# LDA_Board.net
KiCad netlist of a schematic drawn in EAGLE
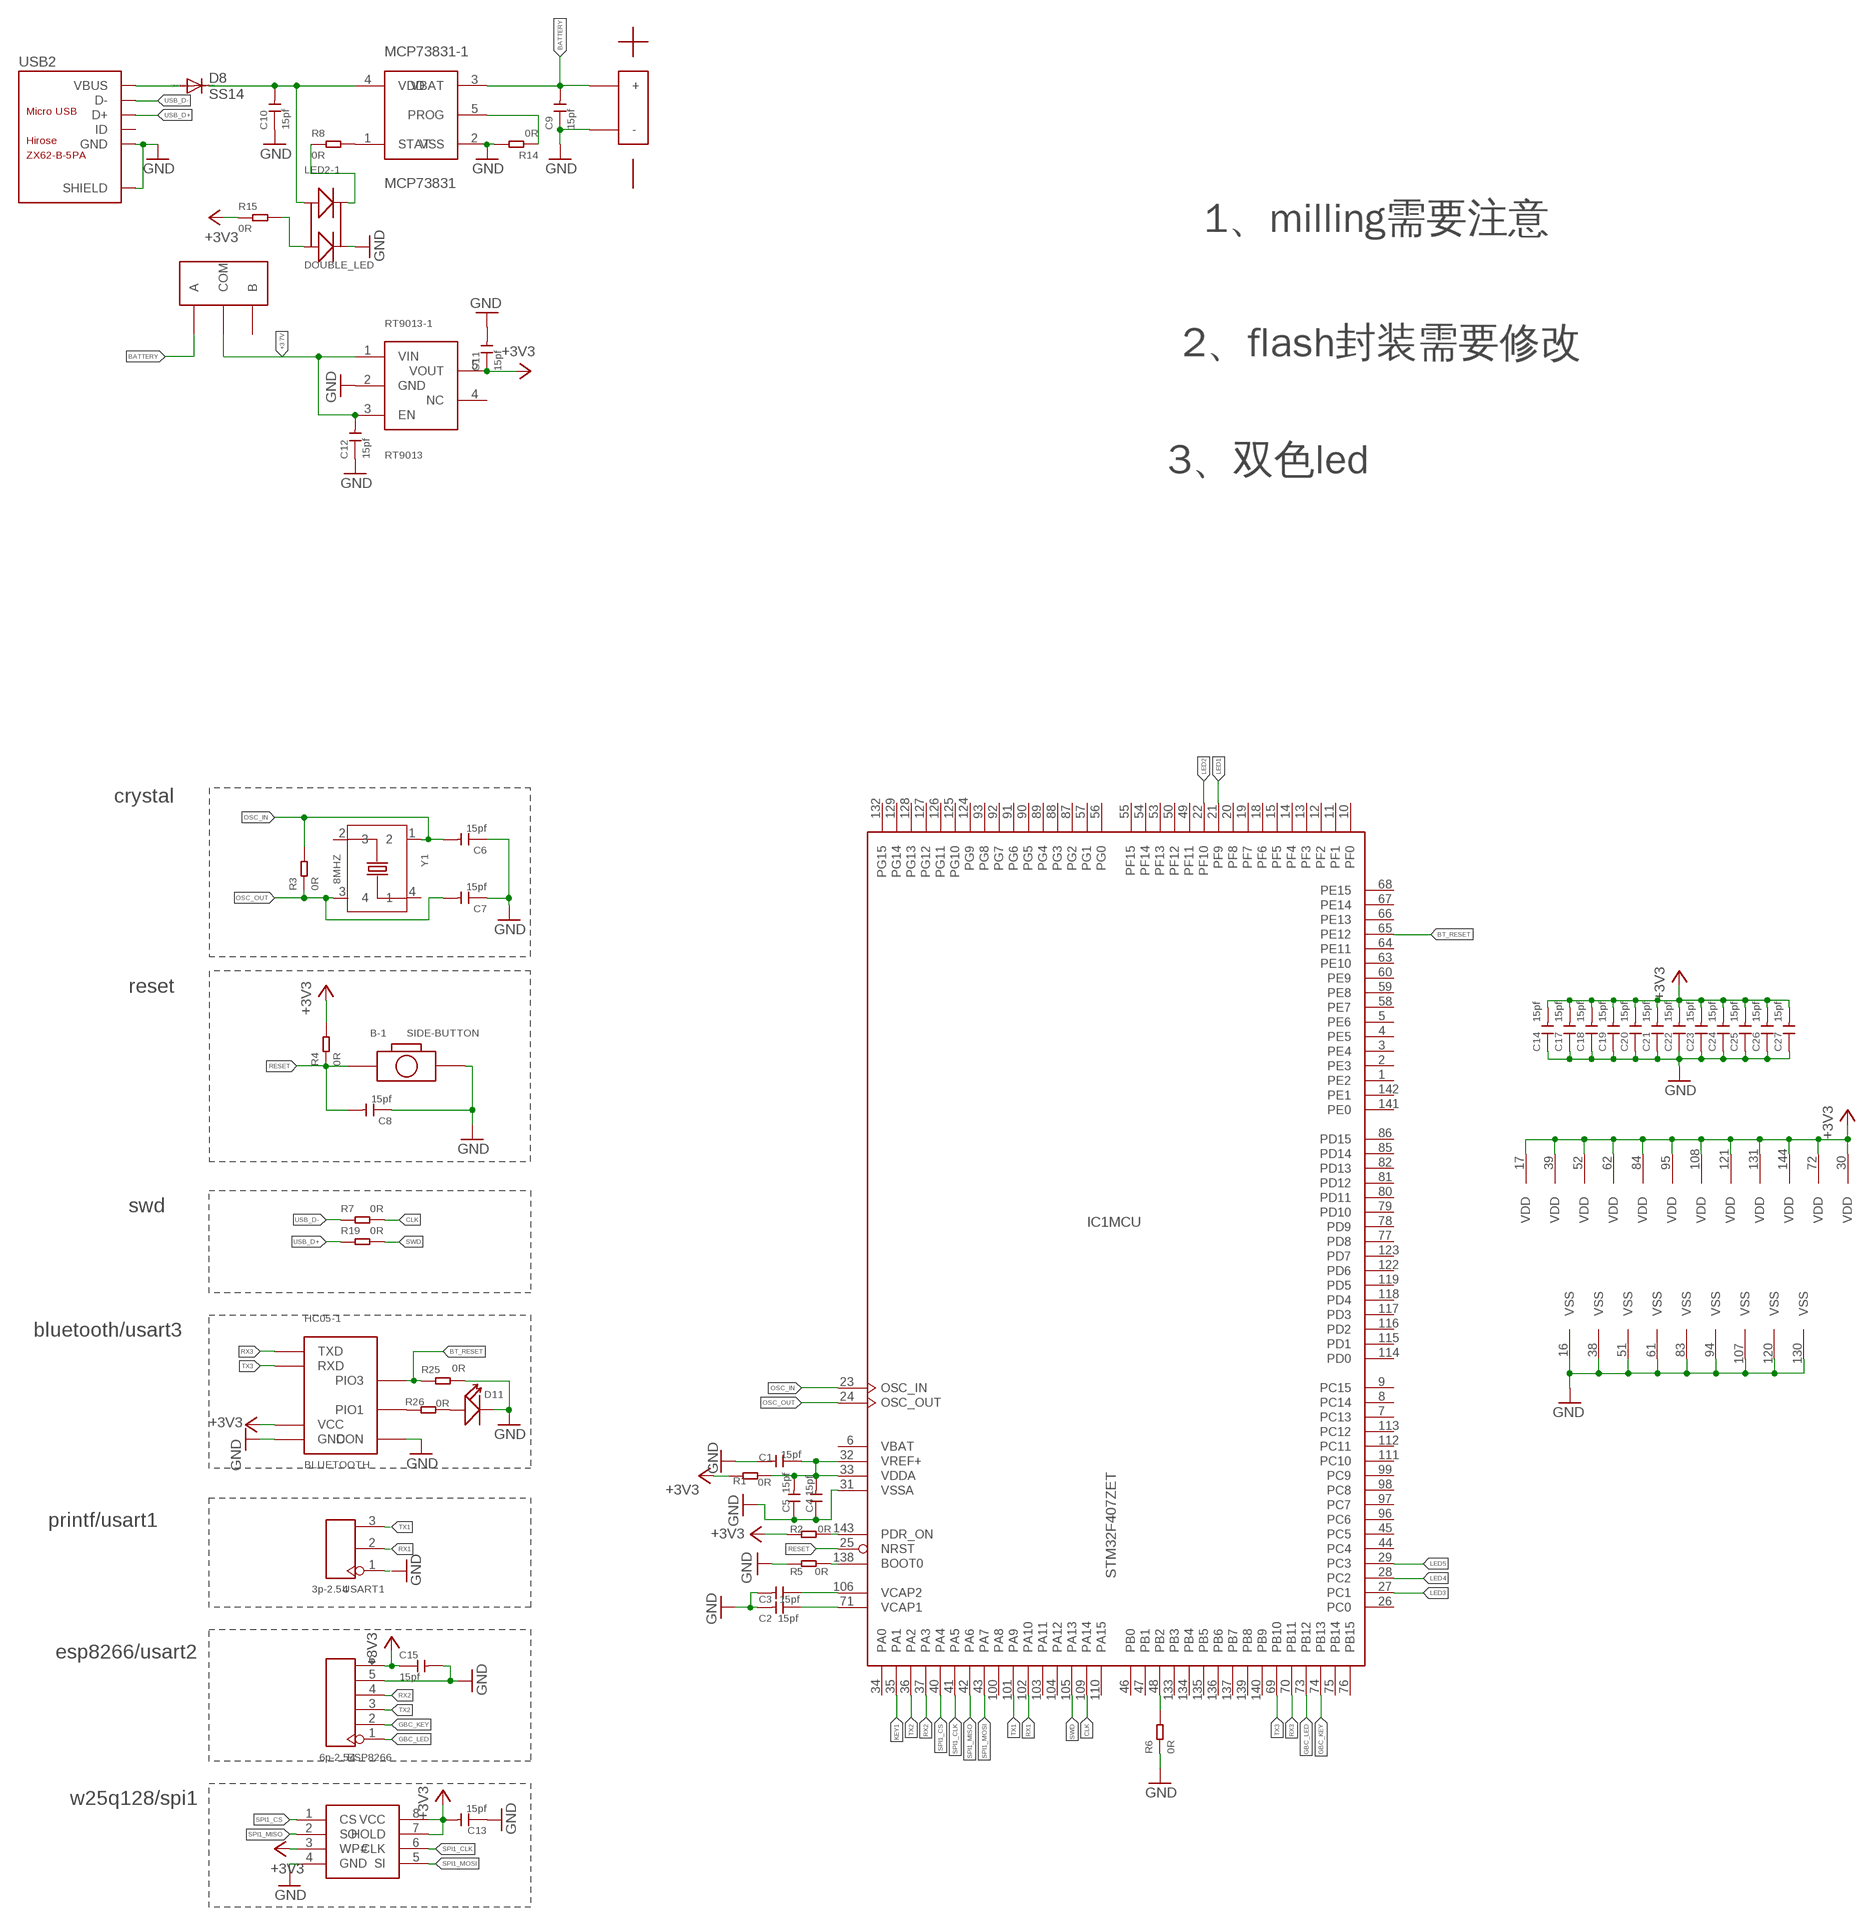
[diagram p0: schematic, sheet 1, part 1 of 2]
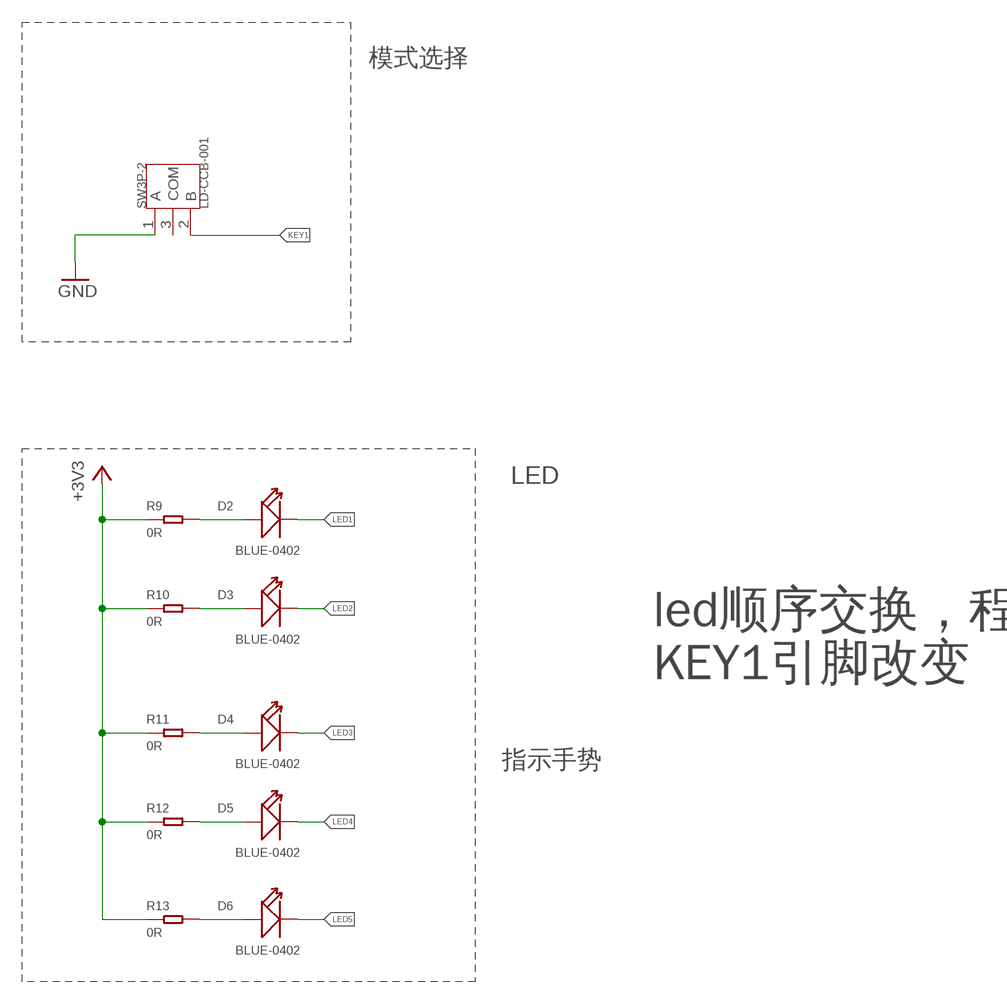
[diagram p1: schematic, sheet 1, part 2 of 2]

(export (version "E")
  (design (tool "Eeschema 10.0.6"))
  (components
    (comp (ref "B-1")
      (value "SIDE-BUTTON")
      (footprint "eagle-import:SIDE-BUTTON")
      (libsource (lib "eagle-import") (part "SIDE-BUTTON"))
    )
    (comp (ref "BATTERY-1")
      (value "BATTERY")
      (footprint "eagle-import:BATTERY")
      (libsource (lib "eagle-import") (part "BATTERY"))
    )
    (comp (ref "C1")
      (value "15pf")
      (footprint "eagle-import:C0402")
      (fields (field (name "MPN") "GRM1555C1H150JA01D"))
      (libsource (lib "eagle-import") (part "CAP-(0402)"))
    )
    (comp (ref "C2")
      (value "15pf")
      (footprint "eagle-import:C0402")
      (fields (field (name "MPN") "GRM1555C1H150JA01D"))
      (libsource (lib "eagle-import") (part "CAP-(0402)"))
    )
    (comp (ref "C3")
      (value "15pf")
      (footprint "eagle-import:C0402")
      (fields (field (name "MPN") "GRM1555C1H150JA01D"))
      (libsource (lib "eagle-import") (part "CAP-(0402)"))
    )
    (comp (ref "C4")
      (value "15pf")
      (footprint "eagle-import:C0402")
      (fields (field (name "MPN") "GRM1555C1H150JA01D"))
      (libsource (lib "eagle-import") (part "CAP-(0402)"))
    )
    (comp (ref "C5")
      (value "15pf")
      (footprint "eagle-import:C0402")
      (fields (field (name "MPN") "GRM1555C1H150JA01D"))
      (libsource (lib "eagle-import") (part "CAP-(0402)"))
    )
    (comp (ref "C6")
      (value "15pf")
      (footprint "eagle-import:C0402")
      (fields (field (name "MPN") "GRM1555C1H150JA01D"))
      (libsource (lib "eagle-import") (part "CAP-(0402)"))
    )
    (comp (ref "C7")
      (value "15pf")
      (footprint "eagle-import:C0402")
      (fields (field (name "MPN") "GRM1555C1H150JA01D"))
      (libsource (lib "eagle-import") (part "CAP-(0402)"))
    )
    (comp (ref "C8")
      (value "15pf")
      (footprint "eagle-import:C0402")
      (fields (field (name "MPN") "GRM1555C1H150JA01D"))
      (libsource (lib "eagle-import") (part "CAP-(0402)"))
    )
    (comp (ref "C9")
      (value "15pf")
      (footprint "eagle-import:C0402")
      (fields (field (name "MPN") "GRM1555C1H150JA01D"))
      (libsource (lib "eagle-import") (part "CAP-(0402)"))
    )
    (comp (ref "C10")
      (value "15pf")
      (footprint "eagle-import:C0402")
      (fields (field (name "MPN") "GRM1555C1H150JA01D"))
      (libsource (lib "eagle-import") (part "CAP-(0402)"))
    )
    (comp (ref "C11")
      (value "15pf")
      (footprint "eagle-import:C0402")
      (fields (field (name "MPN") "GRM1555C1H150JA01D"))
      (libsource (lib "eagle-import") (part "CAP-(0402)"))
    )
    (comp (ref "C12")
      (value "15pf")
      (footprint "eagle-import:C0402")
      (fields (field (name "MPN") "GRM1555C1H150JA01D"))
      (libsource (lib "eagle-import") (part "CAP-(0402)"))
    )
    (comp (ref "C13")
      (value "15pf")
      (footprint "eagle-import:C0402")
      (fields (field (name "MPN") "GRM1555C1H150JA01D"))
      (libsource (lib "eagle-import") (part "CAP-(0402)"))
    )
    (comp (ref "C14")
      (value "15pf")
      (footprint "eagle-import:C0402")
      (fields (field (name "MPN") "GRM1555C1H150JA01D"))
      (libsource (lib "eagle-import") (part "CAP-(0402)"))
    )
    (comp (ref "C15")
      (value "15pf")
      (footprint "eagle-import:C0402")
      (fields (field (name "MPN") "GRM1555C1H150JA01D"))
      (libsource (lib "eagle-import") (part "CAP-(0402)"))
    )
    (comp (ref "C17")
      (value "15pf")
      (footprint "eagle-import:C0402")
      (fields (field (name "MPN") "GRM1555C1H150JA01D"))
      (libsource (lib "eagle-import") (part "CAP-(0402)"))
    )
    (comp (ref "C18")
      (value "15pf")
      (footprint "eagle-import:C0402")
      (fields (field (name "MPN") "GRM1555C1H150JA01D"))
      (libsource (lib "eagle-import") (part "CAP-(0402)"))
    )
    (comp (ref "C19")
      (value "15pf")
      (footprint "eagle-import:C0402")
      (fields (field (name "MPN") "GRM1555C1H150JA01D"))
      (libsource (lib "eagle-import") (part "CAP-(0402)"))
    )
    (comp (ref "C20")
      (value "15pf")
      (footprint "eagle-import:C0402")
      (fields (field (name "MPN") "GRM1555C1H150JA01D"))
      (libsource (lib "eagle-import") (part "CAP-(0402)"))
    )
    (comp (ref "C21")
      (value "15pf")
      (footprint "eagle-import:C0402")
      (fields (field (name "MPN") "GRM1555C1H150JA01D"))
      (libsource (lib "eagle-import") (part "CAP-(0402)"))
    )
    (comp (ref "C22")
      (value "15pf")
      (footprint "eagle-import:C0402")
      (fields (field (name "MPN") "GRM1555C1H150JA01D"))
      (libsource (lib "eagle-import") (part "CAP-(0402)"))
    )
    (comp (ref "C23")
      (value "15pf")
      (footprint "eagle-import:C0402")
      (fields (field (name "MPN") "GRM1555C1H150JA01D"))
      (libsource (lib "eagle-import") (part "CAP-(0402)"))
    )
    (comp (ref "C24")
      (value "15pf")
      (footprint "eagle-import:C0402")
      (fields (field (name "MPN") "GRM1555C1H150JA01D"))
      (libsource (lib "eagle-import") (part "CAP-(0402)"))
    )
    (comp (ref "C25")
      (value "15pf")
      (footprint "eagle-import:C0402")
      (fields (field (name "MPN") "GRM1555C1H150JA01D"))
      (libsource (lib "eagle-import") (part "CAP-(0402)"))
    )
    (comp (ref "C26")
      (value "15pf")
      (footprint "eagle-import:C0402")
      (fields (field (name "MPN") "GRM1555C1H150JA01D"))
      (libsource (lib "eagle-import") (part "CAP-(0402)"))
    )
    (comp (ref "C27")
      (value "15pf")
      (footprint "eagle-import:C0402")
      (fields (field (name "MPN") "GRM1555C1H150JA01D"))
      (libsource (lib "eagle-import") (part "CAP-(0402)"))
    )
    (comp (ref "D2")
      (value "BLUE-0402")
      (footprint "eagle-import:LED-0402")
      (fields (field (name "MPN") "BL-HB337A-AV-TRB"))
      (libsource (lib "eagle-import") (part "LED-(0402)"))
    )
    (comp (ref "D3")
      (value "BLUE-0402")
      (footprint "eagle-import:LED-0402")
      (fields (field (name "MPN") "BL-HB337A-AV-TRB"))
      (libsource (lib "eagle-import") (part "LED-(0402)"))
    )
    (comp (ref "D4")
      (value "BLUE-0402")
      (footprint "eagle-import:LED-0402")
      (fields (field (name "MPN") "BL-HB337A-AV-TRB"))
      (libsource (lib "eagle-import") (part "LED-(0402)"))
    )
    (comp (ref "D5")
      (value "BLUE-0402")
      (footprint "eagle-import:LED-0402")
      (fields (field (name "MPN") "BL-HB337A-AV-TRB"))
      (libsource (lib "eagle-import") (part "LED-(0402)"))
    )
    (comp (ref "D6")
      (value "BLUE-0402")
      (footprint "eagle-import:LED-0402")
      (fields (field (name "MPN") "BL-HB337A-AV-TRB"))
      (libsource (lib "eagle-import") (part "LED-(0402)"))
    )
    (comp (ref "D8")
      (value "SS14")
      (footprint "eagle-import:SMA")
      (libsource (lib "eagle-import") (part "SS14"))
    )
    (comp (ref "D11")
      (value "BLUE-0402")
      (footprint "eagle-import:LED-0402")
      (fields (field (name "MPN") "BL-HB337A-AV-TRB"))
      (libsource (lib "eagle-import") (part "LED-(0402)"))
    )
    (comp (ref "ESP8266")
      (value "6p-2.54")
      (footprint "eagle-import:H6-2.54")
      (fields (field (name "MPN") "F185-1106A1BSYC1"))
      (libsource (lib "eagle-import") (part "DIP-BLACK-FEMALE-HEADER-VERT(6P-2.54)"))
    )
    (comp (ref "HC05-1")
      (value "BLUETOOTH")
      (footprint "eagle-import:BLUETOOTH")
      (libsource (lib "eagle-import") (part "BLUETOOTH"))
    )
    (comp (ref "IC1")
      (value "STM32F407ZET")
      (footprint "eagle-import:LQFP144")
      (libsource (lib "eagle-import") (part "STM32F407ZTE"))
    )
    (comp (ref "LED2-1")
      (value "DOUBLE_LED")
      (footprint "eagle-import:LED2-SMD-1010")
      (libsource (lib "eagle-import") (part "DOUBLE_LED"))
    )
    (comp (ref "MCP73831-1")
      (value "MCP73831")
      (footprint "eagle-import:SOT23-5")
      (libsource (lib "eagle-import") (part "MCP73831"))
    )
    (comp (ref "R1")
      (value "0R")
      (footprint "eagle-import:R0402")
      (fields (field (name "MPN") "RC0402JR-070RL"))
      (libsource (lib "eagle-import") (part "RES-(0402)"))
    )
    (comp (ref "R2")
      (value "0R")
      (footprint "eagle-import:R0402")
      (fields (field (name "MPN") "RC0402JR-070RL"))
      (libsource (lib "eagle-import") (part "RES-(0402)"))
    )
    (comp (ref "R3")
      (value "0R")
      (footprint "eagle-import:R0402")
      (fields (field (name "MPN") "RC0402JR-070RL"))
      (libsource (lib "eagle-import") (part "RES-(0402)"))
    )
    (comp (ref "R4")
      (value "0R")
      (footprint "eagle-import:R0402")
      (fields (field (name "MPN") "RC0402JR-070RL"))
      (libsource (lib "eagle-import") (part "RES-(0402)"))
    )
    (comp (ref "R5")
      (value "0R")
      (footprint "eagle-import:R0402")
      (fields (field (name "MPN") "RC0402JR-070RL"))
      (libsource (lib "eagle-import") (part "RES-(0402)"))
    )
    (comp (ref "R6")
      (value "0R")
      (footprint "eagle-import:R0402")
      (fields (field (name "MPN") "RC0402JR-070RL"))
      (libsource (lib "eagle-import") (part "RES-(0402)"))
    )
    (comp (ref "R7")
      (value "0R")
      (footprint "eagle-import:R0402")
      (fields (field (name "MPN") "RC0402JR-070RL"))
      (libsource (lib "eagle-import") (part "RES-(0402)"))
    )
    (comp (ref "R8")
      (value "0R")
      (footprint "eagle-import:R0402")
      (fields (field (name "MPN") "RC0402JR-070RL"))
      (libsource (lib "eagle-import") (part "RES-(0402)"))
    )
    (comp (ref "R9")
      (value "0R")
      (footprint "eagle-import:R0402")
      (fields (field (name "MPN") "RC0402JR-070RL"))
      (libsource (lib "eagle-import") (part "RES-(0402)"))
    )
    (comp (ref "R10")
      (value "0R")
      (footprint "eagle-import:R0402")
      (fields (field (name "MPN") "RC0402JR-070RL"))
      (libsource (lib "eagle-import") (part "RES-(0402)"))
    )
    (comp (ref "R11")
      (value "0R")
      (footprint "eagle-import:R0402")
      (fields (field (name "MPN") "RC0402JR-070RL"))
      (libsource (lib "eagle-import") (part "RES-(0402)"))
    )
    (comp (ref "R12")
      (value "0R")
      (footprint "eagle-import:R0402")
      (fields (field (name "MPN") "RC0402JR-070RL"))
      (libsource (lib "eagle-import") (part "RES-(0402)"))
    )
    (comp (ref "R13")
      (value "0R")
      (footprint "eagle-import:R0402")
      (fields (field (name "MPN") "RC0402JR-070RL"))
      (libsource (lib "eagle-import") (part "RES-(0402)"))
    )
    (comp (ref "R14")
      (value "0R")
      (footprint "eagle-import:R0402")
      (fields (field (name "MPN") "RC0402JR-070RL"))
      (libsource (lib "eagle-import") (part "RES-(0402)"))
    )
    (comp (ref "R15")
      (value "0R")
      (footprint "eagle-import:R0402")
      (fields (field (name "MPN") "RC0402JR-070RL"))
      (libsource (lib "eagle-import") (part "RES-(0402)"))
    )
    (comp (ref "R19")
      (value "0R")
      (footprint "eagle-import:R0402")
      (fields (field (name "MPN") "RC0402JR-070RL"))
      (libsource (lib "eagle-import") (part "RES-(0402)"))
    )
    (comp (ref "R25")
      (value "0R")
      (footprint "eagle-import:R0402")
      (fields (field (name "MPN") "RC0402JR-070RL"))
      (libsource (lib "eagle-import") (part "RES-(0402)"))
    )
    (comp (ref "R26")
      (value "0R")
      (footprint "eagle-import:R0402")
      (fields (field (name "MPN") "RC0402JR-070RL"))
      (libsource (lib "eagle-import") (part "RES-(0402)"))
    )
    (comp (ref "RT9013-1")
      (value "RT9013")
      (footprint "eagle-import:SOT23-5")
      (libsource (lib "eagle-import") (part "RT9013"))
    )
    (comp (ref "SW-1")
      (value "SWITCH-3P")
      (footprint "eagle-import:SWITCH-3P")
      (libsource (lib "eagle-import") (part "SWITCH-3P"))
    )
    (comp (ref "SW3P-2")
      (value "LD-CCB-001")
      (footprint "eagle-import:SW3-2.54-9.0X3.5X3.5+2.0MM")
      (libsource (lib "eagle-import") (part "SWITCH(3P)"))
    )
    (comp (ref "USART1")
      (value "3p-2.54")
      (footprint "eagle-import:H3-2.54")
      (fields (field (name "MPN") "F185-1103A0BSYA1"))
      (libsource (lib "eagle-import") (part "DIP-BLACK-FEMALE-HEADER-VERT(3P-2.54)"))
    )
    (comp (ref "USB2")
      (value "ZX62-B-5PA")
      (footprint "eagle-import:MICRO-USB5+6P-SMD-0.65-AB")
      (libsource (lib "eagle-import") (part "MICRO-USB-SMD(ZX62-B-5PA)"))
    )
    (comp (ref "W25Q128")
      (value "W25Q128")
      (footprint "eagle-import:SOP08")
      (libsource (lib "eagle-import") (part "W25Q128"))
    )
    (comp (ref "Y1")
      (value "8MHZ")
      (footprint "eagle-import:X4-SMD-3.2X2.5X0.7MM")
      (fields (field (name "MPN") "7M-27.120MAAJ-T"))
      (libsource (lib "eagle-import") (part "SMD-CRYSTAL-27.12MHZ-18PF-30PPM-60R(4P-3.2X2.5MM)"))
    )
  )
  (nets
    (net (code "1") (name "+3.7V") (class "Default")
      (node (ref "C12") (pin "2") (pinfunction "2_2") (pintype "passive"))
      (node (ref "RT9013-1") (pin "1") (pinfunction "VIN_1") (pintype "bidirectional"))
      (node (ref "RT9013-1") (pin "3") (pinfunction "EN_3") (pintype "bidirectional"))
      (node (ref "SW-1") (pin "P$2") (pinfunction "COM_P$2") (pintype "bidirectional"))
    )
    (net (code "2") (name "+3V3") (class "Default")
      (node (ref "C11") (pin "1") (pinfunction "1_1") (pintype "passive"))
      (node (ref "C13") (pin "2") (pinfunction "2_2") (pintype "passive"))
      (node (ref "C14") (pin "2") (pinfunction "2_2") (pintype "passive"))
      (node (ref "C15") (pin "1") (pinfunction "1_1") (pintype "passive"))
      (node (ref "C17") (pin "2") (pinfunction "2_2") (pintype "passive"))
      (node (ref "C18") (pin "2") (pinfunction "2_2") (pintype "passive"))
      (node (ref "C19") (pin "2") (pinfunction "2_2") (pintype "passive"))
      (node (ref "C20") (pin "2") (pinfunction "2_2") (pintype "passive"))
      (node (ref "C21") (pin "2") (pinfunction "2_2") (pintype "passive"))
      (node (ref "C22") (pin "2") (pinfunction "2_2") (pintype "passive"))
      (node (ref "C23") (pin "2") (pinfunction "2_2") (pintype "passive"))
      (node (ref "C24") (pin "2") (pinfunction "2_2") (pintype "passive"))
      (node (ref "C25") (pin "2") (pinfunction "2_2") (pintype "passive"))
      (node (ref "C26") (pin "2") (pinfunction "2_2") (pintype "passive"))
      (node (ref "C27") (pin "2") (pinfunction "2_2") (pintype "passive"))
      (node (ref "ESP8266") (pin "6") (pinfunction "6_6") (pintype "bidirectional"))
      (node (ref "HC05-1") (pin "P$12") (pinfunction "VCC_P$12") (pintype "bidirectional"))
      (node (ref "IC1") (pin "108") (pinfunction "VDD_108") (pintype "power_in"))
      (node (ref "IC1") (pin "121") (pinfunction "VDD_121") (pintype "power_in"))
      (node (ref "IC1") (pin "131") (pinfunction "VDD_131") (pintype "power_in"))
      (node (ref "IC1") (pin "144") (pinfunction "VDD_144") (pintype "power_in"))
      (node (ref "IC1") (pin "17") (pinfunction "VDD_17") (pintype "power_in"))
      (node (ref "IC1") (pin "30") (pinfunction "VDD_30") (pintype "power_in"))
      (node (ref "IC1") (pin "39") (pinfunction "VDD_39") (pintype "power_in"))
      (node (ref "IC1") (pin "52") (pinfunction "VDD_52") (pintype "power_in"))
      (node (ref "IC1") (pin "62") (pinfunction "VDD_62") (pintype "power_in"))
      (node (ref "IC1") (pin "72") (pinfunction "VDD_72") (pintype "power_in"))
      (node (ref "IC1") (pin "84") (pinfunction "VDD_84") (pintype "power_in"))
      (node (ref "IC1") (pin "95") (pinfunction "VDD_95") (pintype "power_in"))
      (node (ref "R1") (pin "1") (pinfunction "1_1") (pintype "passive"))
      (node (ref "R10") (pin "1") (pinfunction "1_1") (pintype "passive"))
      (node (ref "R11") (pin "1") (pinfunction "1_1") (pintype "passive"))
      (node (ref "R12") (pin "1") (pinfunction "1_1") (pintype "passive"))
      (node (ref "R13") (pin "1") (pinfunction "1_1") (pintype "passive"))
      (node (ref "R15") (pin "1") (pinfunction "1_1") (pintype "passive"))
      (node (ref "R2") (pin "1") (pinfunction "1_1") (pintype "passive"))
      (node (ref "R4") (pin "2") (pinfunction "2_2") (pintype "passive"))
      (node (ref "R9") (pin "1") (pinfunction "1_1") (pintype "passive"))
      (node (ref "RT9013-1") (pin "5") (pinfunction "VOUT_5") (pintype "bidirectional"))
      (node (ref "W25Q128") (pin "3") (pinfunction "WP#_3") (pintype "bidirectional"))
      (node (ref "W25Q128") (pin "7") (pinfunction "HOLD_7") (pintype "bidirectional"))
      (node (ref "W25Q128") (pin "8") (pinfunction "VCC_8") (pintype "bidirectional"))
    )
    (net (code "3") (name "/VBAT") (class "Default")
      (node (ref "IC1") (pin "6") (pinfunction "VBAT_6") (pintype "power_in"))
    )
    (net (code "4") (name "BATTERY") (class "Default")
      (node (ref "BATTERY-1") (pin "P$1") (pinfunction "+_P$1") (pintype "bidirectional"))
      (node (ref "C9") (pin "2") (pinfunction "2_2") (pintype "passive"))
      (node (ref "MCP73831-1") (pin "3") (pinfunction "VBAT_3") (pintype "bidirectional"))
      (node (ref "SW-1") (pin "P$3") (pinfunction "A_P$3") (pintype "bidirectional"))
    )
    (net (code "5") (name "BT_RESET") (class "Default")
      (node (ref "HC05-1") (pin "P$26") (pinfunction "PIO3_P$26") (pintype "bidirectional"))
      (node (ref "IC1") (pin "65") (pinfunction "PE12_65") (pintype "bidirectional"))
      (node (ref "R25") (pin "1") (pinfunction "1_1") (pintype "passive"))
    )
    (net (code "6") (name "CLK") (class "Default")
      (node (ref "IC1") (pin "109") (pinfunction "PA14_109") (pintype "bidirectional"))
      (node (ref "R7") (pin "2") (pinfunction "2_2") (pintype "passive"))
    )
    (net (code "7") (name "GBC_KEY") (class "Default")
      (node (ref "ESP8266") (pin "2") (pinfunction "2_2") (pintype "bidirectional"))
      (node (ref "IC1") (pin "74") (pinfunction "PB13_74") (pintype "bidirectional"))
    )
    (net (code "8") (name "GBC_LED") (class "Default")
      (node (ref "ESP8266") (pin "1") (pinfunction "1_1") (pintype "bidirectional"))
      (node (ref "IC1") (pin "73") (pinfunction "PB12_73") (pintype "bidirectional"))
    )
    (net (code "9") (name "GND") (class "Default")
      (node (ref "B-1") (pin "P$1") (pinfunction "2_P$1") (pintype "bidirectional"))
      (node (ref "BATTERY-1") (pin "P$2") (pinfunction "-_P$2") (pintype "bidirectional"))
      (node (ref "C1") (pin "2") (pinfunction "2_2") (pintype "passive"))
      (node (ref "C10") (pin "1") (pinfunction "1_1") (pintype "passive"))
      (node (ref "C11") (pin "2") (pinfunction "2_2") (pintype "passive"))
      (node (ref "C12") (pin "1") (pinfunction "1_1") (pintype "passive"))
      (node (ref "C13") (pin "1") (pinfunction "1_1") (pintype "passive"))
      (node (ref "C14") (pin "1") (pinfunction "1_1") (pintype "passive"))
      (node (ref "C15") (pin "2") (pinfunction "2_2") (pintype "passive"))
      (node (ref "C17") (pin "1") (pinfunction "1_1") (pintype "passive"))
      (node (ref "C18") (pin "1") (pinfunction "1_1") (pintype "passive"))
      (node (ref "C19") (pin "1") (pinfunction "1_1") (pintype "passive"))
      (node (ref "C2") (pin "2") (pinfunction "2_2") (pintype "passive"))
      (node (ref "C20") (pin "1") (pinfunction "1_1") (pintype "passive"))
      (node (ref "C21") (pin "1") (pinfunction "1_1") (pintype "passive"))
      (node (ref "C22") (pin "1") (pinfunction "1_1") (pintype "passive"))
      (node (ref "C23") (pin "1") (pinfunction "1_1") (pintype "passive"))
      (node (ref "C24") (pin "1") (pinfunction "1_1") (pintype "passive"))
      (node (ref "C25") (pin "1") (pinfunction "1_1") (pintype "passive"))
      (node (ref "C26") (pin "1") (pinfunction "1_1") (pintype "passive"))
      (node (ref "C27") (pin "1") (pinfunction "1_1") (pintype "passive"))
      (node (ref "C3") (pin "2") (pinfunction "2_2") (pintype "passive"))
      (node (ref "C4") (pin "1") (pinfunction "1_1") (pintype "passive"))
      (node (ref "C5") (pin "1") (pinfunction "1_1") (pintype "passive"))
      (node (ref "C6") (pin "1") (pinfunction "1_1") (pintype "passive"))
      (node (ref "C7") (pin "1") (pinfunction "1_1") (pintype "passive"))
      (node (ref "C8") (pin "1") (pinfunction "1_1") (pintype "passive"))
      (node (ref "C9") (pin "1") (pinfunction "1_1") (pintype "passive"))
      (node (ref "D11") (pin "-") (pinfunction "-_-") (pintype "passive"))
      (node (ref "ESP8266") (pin "5") (pinfunction "5_5") (pintype "bidirectional"))
      (node (ref "HC05-1") (pin "P$13") (pinfunction "GND_P$13") (pintype "bidirectional"))
      (node (ref "HC05-1") (pin "P$22") (pinfunction "CON_P$22") (pintype "bidirectional"))
      (node (ref "IC1") (pin "107") (pinfunction "VSS_107") (pintype "power_in"))
      (node (ref "IC1") (pin "120") (pinfunction "VSS_120") (pintype "power_in"))
      (node (ref "IC1") (pin "130") (pinfunction "VSS_130") (pintype "power_in"))
      (node (ref "IC1") (pin "16") (pinfunction "VSS_16") (pintype "power_in"))
      (node (ref "IC1") (pin "31") (pinfunction "VSSA_31") (pintype "power_in"))
      (node (ref "IC1") (pin "38") (pinfunction "VSS_38") (pintype "power_in"))
      (node (ref "IC1") (pin "51") (pinfunction "VSS_51") (pintype "power_in"))
      (node (ref "IC1") (pin "61") (pinfunction "VSS_61") (pintype "power_in"))
      (node (ref "IC1") (pin "83") (pinfunction "VSS_83") (pintype "power_in"))
      (node (ref "IC1") (pin "94") (pinfunction "VSS_94") (pintype "power_in"))
      (node (ref "LED2-1") (pin "3") (pinfunction "3_3") (pintype "passive"))
      (node (ref "MCP73831-1") (pin "2") (pinfunction "VSS_2") (pintype "bidirectional"))
      (node (ref "R14") (pin "2") (pinfunction "2_2") (pintype "passive"))
      (node (ref "R25") (pin "2") (pinfunction "2_2") (pintype "passive"))
      (node (ref "R5") (pin "1") (pinfunction "1_1") (pintype "passive"))
      (node (ref "R6") (pin "1") (pinfunction "1_1") (pintype "passive"))
      (node (ref "RT9013-1") (pin "2") (pinfunction "GND_2") (pintype "bidirectional"))
      (node (ref "SW3P-2") (pin "1") (pinfunction "A_1") (pintype "bidirectional"))
      (node (ref "USART1") (pin "1") (pinfunction "P$1_1") (pintype "bidirectional"))
      (node (ref "USB2") (pin "5") (pinfunction "GND_5") (pintype "power_in"))
      (node (ref "USB2") (pin "P1") (pinfunction "SHIELD_P1") (pintype "power_in"))
      (node (ref "USB2") (pin "P2") (pinfunction "SHIELD_P2") (pintype "power_in"))
      (node (ref "USB2") (pin "P3") (pinfunction "SHIELD_P3") (pintype "power_in"))
      (node (ref "USB2") (pin "P4") (pinfunction "SHIELD_P4") (pintype "power_in"))
      (node (ref "USB2") (pin "P5") (pinfunction "SHIELD_P5") (pintype "power_in"))
      (node (ref "USB2") (pin "P6") (pinfunction "SHIELD_P6") (pintype "power_in"))
      (node (ref "W25Q128") (pin "4") (pinfunction "GND_4") (pintype "bidirectional"))
    )
    (net (code "10") (name "KEY1") (class "Default")
      (node (ref "IC1") (pin "35") (pinfunction "PA1_35") (pintype "bidirectional"))
      (node (ref "SW3P-2") (pin "2") (pinfunction "B_2") (pintype "bidirectional"))
    )
    (net (code "11") (name "LED1") (class "Default")
      (node (ref "D2") (pin "-") (pinfunction "-_-") (pintype "passive"))
      (node (ref "IC1") (pin "21") (pinfunction "PF9_21") (pintype "bidirectional"))
    )
    (net (code "12") (name "LED2") (class "Default")
      (node (ref "D3") (pin "-") (pinfunction "-_-") (pintype "passive"))
      (node (ref "IC1") (pin "22") (pinfunction "PF10_22") (pintype "bidirectional"))
    )
    (net (code "13") (name "LED3") (class "Default")
      (node (ref "D4") (pin "-") (pinfunction "-_-") (pintype "passive"))
      (node (ref "IC1") (pin "27") (pinfunction "PC1_27") (pintype "bidirectional"))
    )
    (net (code "14") (name "LED4") (class "Default")
      (node (ref "D5") (pin "-") (pinfunction "-_-") (pintype "passive"))
      (node (ref "IC1") (pin "28") (pinfunction "PC2_28") (pintype "bidirectional"))
    )
    (net (code "15") (name "LED5") (class "Default")
      (node (ref "D6") (pin "-") (pinfunction "-_-") (pintype "passive"))
      (node (ref "IC1") (pin "29") (pinfunction "PC3_29") (pintype "bidirectional"))
    )
    (net (code "16") (name "Net-(D2-Pad+)") (class "Default")
      (node (ref "D2") (pin "+") (pinfunction "+_+") (pintype "passive"))
      (node (ref "R9") (pin "2") (pinfunction "2_2") (pintype "passive"))
    )
    (net (code "17") (name "Net-(D3-Pad+)") (class "Default")
      (node (ref "D3") (pin "+") (pinfunction "+_+") (pintype "passive"))
      (node (ref "R10") (pin "2") (pinfunction "2_2") (pintype "passive"))
    )
    (net (code "18") (name "Net-(D4-Pad+)") (class "Default")
      (node (ref "D4") (pin "+") (pinfunction "+_+") (pintype "passive"))
      (node (ref "R11") (pin "2") (pinfunction "2_2") (pintype "passive"))
    )
    (net (code "19") (name "Net-(D5-Pad+)") (class "Default")
      (node (ref "D5") (pin "+") (pinfunction "+_+") (pintype "passive"))
      (node (ref "R12") (pin "2") (pinfunction "2_2") (pintype "passive"))
    )
    (net (code "20") (name "Net-(D6-Pad+)") (class "Default")
      (node (ref "D6") (pin "+") (pinfunction "+_+") (pintype "passive"))
      (node (ref "R13") (pin "2") (pinfunction "2_2") (pintype "passive"))
    )
    (net (code "21") (name "Net-(D11-Pad+)") (class "Default")
      (node (ref "D11") (pin "+") (pinfunction "+_+") (pintype "passive"))
      (node (ref "R26") (pin "2") (pinfunction "2_2") (pintype "passive"))
    )
    (net (code "22") (name "Net-(HC05-1-PIO1)") (class "Default")
      (node (ref "HC05-1") (pin "P$24") (pinfunction "PIO1_P$24") (pintype "bidirectional"))
      (node (ref "R26") (pin "1") (pinfunction "1_1") (pintype "passive"))
    )
    (net (code "23") (name "Net-(IC1A-BOOT0)") (class "Default")
      (node (ref "IC1") (pin "138") (pinfunction "BOOT0_138") (pintype "input"))
      (node (ref "R5") (pin "2") (pinfunction "2_2") (pintype "passive"))
    )
    (net (code "24") (name "Net-(IC1A-PB2)") (class "Default")
      (node (ref "IC1") (pin "48") (pinfunction "PB2_48") (pintype "bidirectional"))
      (node (ref "R6") (pin "2") (pinfunction "2_2") (pintype "passive"))
    )
    (net (code "25") (name "Net-(IC1A-PDR_ON)") (class "Default")
      (node (ref "IC1") (pin "143") (pinfunction "PDR_ON_143") (pintype "input"))
      (node (ref "R2") (pin "2") (pinfunction "2_2") (pintype "passive"))
    )
    (net (code "26") (name "Net-(IC1A-VCAP1)") (class "Default")
      (node (ref "C2") (pin "1") (pinfunction "1_1") (pintype "passive"))
      (node (ref "IC1") (pin "71") (pinfunction "VCAP1_71") (pintype "power_in"))
    )
    (net (code "27") (name "Net-(IC1A-VCAP2)") (class "Default")
      (node (ref "C3") (pin "1") (pinfunction "1_1") (pintype "passive"))
      (node (ref "IC1") (pin "106") (pinfunction "VCAP2_106") (pintype "power_in"))
    )
    (net (code "28") (name "Net-(IC1A-VDDA)") (class "Default")
      (node (ref "C1") (pin "1") (pinfunction "1_1") (pintype "passive"))
      (node (ref "C4") (pin "2") (pinfunction "2_2") (pintype "passive"))
      (node (ref "C5") (pin "2") (pinfunction "2_2") (pintype "passive"))
      (node (ref "IC1") (pin "32") (pinfunction "VREF+_32") (pintype "power_in"))
      (node (ref "IC1") (pin "33") (pinfunction "VDDA_33") (pintype "power_in"))
      (node (ref "R1") (pin "2") (pinfunction "2_2") (pintype "passive"))
    )
    (net (code "29") (name "Net-(LED2-1-Pad2)") (class "Default")
      (node (ref "LED2-1") (pin "2") (pinfunction "2_2") (pintype "passive"))
      (node (ref "R15") (pin "2") (pinfunction "2_2") (pintype "passive"))
    )
    (net (code "30") (name "Net-(LED2-1-Pad4)") (class "Default")
      (node (ref "LED2-1") (pin "4") (pinfunction "4_4") (pintype "passive"))
      (node (ref "R8") (pin "1") (pinfunction "1_1") (pintype "passive"))
    )
    (net (code "31") (name "Net-(MCP73831-1-PROG)") (class "Default")
      (node (ref "MCP73831-1") (pin "5") (pinfunction "PROG_5") (pintype "bidirectional"))
      (node (ref "R14") (pin "1") (pinfunction "1_1") (pintype "passive"))
    )
    (net (code "32") (name "Net-(MCP73831-1-STAT)") (class "Default")
      (node (ref "MCP73831-1") (pin "1") (pinfunction "STAT_1") (pintype "bidirectional"))
      (node (ref "R8") (pin "2") (pinfunction "2_2") (pintype "passive"))
    )
    (net (code "33") (name "Net-(MCP73831-1-VDD)") (class "Default")
      (node (ref "C10") (pin "2") (pinfunction "2_2") (pintype "passive"))
      (node (ref "D8") (pin "C") (pinfunction "C_C") (pintype "passive"))
      (node (ref "LED2-1") (pin "1") (pinfunction "1_1") (pintype "passive"))
      (node (ref "MCP73831-1") (pin "4") (pinfunction "VDD_4") (pintype "bidirectional"))
    )
    (net (code "34") (name "Net-(USB2-VBUS)") (class "Default")
      (node (ref "D8") (pin "A") (pinfunction "A_A") (pintype "passive"))
      (node (ref "USB2") (pin "1") (pinfunction "VBUS_1") (pintype "power_in"))
    )
    (net (code "35") (name "OSC_IN") (class "Default")
      (node (ref "C6") (pin "2") (pinfunction "2_2") (pintype "passive"))
      (node (ref "IC1") (pin "23") (pinfunction "OSC_IN_23") (pintype "bidirectional"))
      (node (ref "R3") (pin "2") (pinfunction "2_2") (pintype "passive"))
      (node (ref "Y1") (pin "1") (pinfunction "2_1") (pintype "bidirectional"))
    )
    (net (code "36") (name "OSC_OUT") (class "Default")
      (node (ref "C7") (pin "2") (pinfunction "2_2") (pintype "passive"))
      (node (ref "IC1") (pin "24") (pinfunction "OSC_OUT_24") (pintype "bidirectional"))
      (node (ref "R3") (pin "1") (pinfunction "1_1") (pintype "passive"))
      (node (ref "Y1") (pin "3") (pinfunction "4_3") (pintype "bidirectional"))
    )
    (net (code "37") (name "RESET") (class "Default")
      (node (ref "B-1") (pin "P$2") (pinfunction "1_P$2") (pintype "bidirectional"))
      (node (ref "C8") (pin "2") (pinfunction "2_2") (pintype "passive"))
      (node (ref "IC1") (pin "25") (pinfunction "NRST_25") (pintype "bidirectional"))
      (node (ref "R4") (pin "1") (pinfunction "1_1") (pintype "passive"))
    )
    (net (code "38") (name "RX1") (class "Default")
      (node (ref "IC1") (pin "102") (pinfunction "PA10_102") (pintype "bidirectional"))
      (node (ref "USART1") (pin "2") (pinfunction "P$2_2") (pintype "bidirectional"))
    )
    (net (code "39") (name "RX2") (class "Default")
      (node (ref "ESP8266") (pin "4") (pinfunction "4_4") (pintype "bidirectional"))
      (node (ref "IC1") (pin "37") (pinfunction "PA3_37") (pintype "bidirectional"))
    )
    (net (code "40") (name "RX3") (class "Default")
      (node (ref "HC05-1") (pin "P$1") (pinfunction "TXD_P$1") (pintype "bidirectional"))
      (node (ref "IC1") (pin "70") (pinfunction "PB11_70") (pintype "bidirectional"))
    )
    (net (code "41") (name "SPI1_CLK") (class "Default")
      (node (ref "IC1") (pin "41") (pinfunction "PA5_41") (pintype "bidirectional"))
      (node (ref "W25Q128") (pin "6") (pinfunction "CLK_6") (pintype "bidirectional"))
    )
    (net (code "42") (name "SPI1_CS") (class "Default")
      (node (ref "IC1") (pin "40") (pinfunction "PA4_40") (pintype "bidirectional"))
      (node (ref "W25Q128") (pin "1") (pinfunction "CS_1") (pintype "bidirectional"))
    )
    (net (code "43") (name "SPI1_MISO") (class "Default")
      (node (ref "IC1") (pin "42") (pinfunction "PA6_42") (pintype "bidirectional"))
      (node (ref "W25Q128") (pin "2") (pinfunction "SO_2") (pintype "bidirectional"))
    )
    (net (code "44") (name "SPI1_MOSI") (class "Default")
      (node (ref "IC1") (pin "43") (pinfunction "PA7_43") (pintype "bidirectional"))
      (node (ref "W25Q128") (pin "5") (pinfunction "SI_5") (pintype "bidirectional"))
    )
    (net (code "45") (name "SWD") (class "Default")
      (node (ref "IC1") (pin "105") (pinfunction "PA13_105") (pintype "bidirectional"))
      (node (ref "R19") (pin "2") (pinfunction "2_2") (pintype "passive"))
    )
    (net (code "46") (name "TX1") (class "Default")
      (node (ref "IC1") (pin "101") (pinfunction "PA9_101") (pintype "bidirectional"))
      (node (ref "USART1") (pin "3") (pinfunction "P$3_3") (pintype "bidirectional"))
    )
    (net (code "47") (name "TX2") (class "Default")
      (node (ref "ESP8266") (pin "3") (pinfunction "3_3") (pintype "bidirectional"))
      (node (ref "IC1") (pin "36") (pinfunction "PA2_36") (pintype "bidirectional"))
    )
    (net (code "48") (name "TX3") (class "Default")
      (node (ref "HC05-1") (pin "P$2") (pinfunction "RXD_P$2") (pintype "bidirectional"))
      (node (ref "IC1") (pin "69") (pinfunction "PB10_69") (pintype "bidirectional"))
    )
    (net (code "49") (name "USB_D+") (class "Default")
      (node (ref "R19") (pin "1") (pinfunction "1_1") (pintype "passive"))
      (node (ref "USB2") (pin "3") (pinfunction "D+_3") (pintype "bidirectional"))
    )
    (net (code "50") (name "USB_D-") (class "Default")
      (node (ref "R7") (pin "1") (pinfunction "1_1") (pintype "passive"))
      (node (ref "USB2") (pin "2") (pinfunction "D-_2") (pintype "bidirectional"))
    )
    (net (code "51") (name "unconnected-(IC1A-PA0-Pad34)") (class "Default")
      (node (ref "IC1") (pin "34") (pinfunction "PA0_34") (pintype "bidirectional"))
    )
    (net (code "52") (name "unconnected-(IC1A-PA8-Pad100)") (class "Default")
      (node (ref "IC1") (pin "100") (pinfunction "PA8_100") (pintype "bidirectional"))
    )
    (net (code "53") (name "unconnected-(IC1A-PA11-Pad103)") (class "Default")
      (node (ref "IC1") (pin "103") (pinfunction "PA11_103") (pintype "bidirectional"))
    )
    (net (code "54") (name "unconnected-(IC1A-PA12-Pad104)") (class "Default")
      (node (ref "IC1") (pin "104") (pinfunction "PA12_104") (pintype "bidirectional"))
    )
    (net (code "55") (name "unconnected-(IC1A-PA15-Pad110)") (class "Default")
      (node (ref "IC1") (pin "110") (pinfunction "PA15_110") (pintype "bidirectional"))
    )
    (net (code "56") (name "unconnected-(IC1A-PB0-Pad46)") (class "Default")
      (node (ref "IC1") (pin "46") (pinfunction "PB0_46") (pintype "bidirectional"))
    )
    (net (code "57") (name "unconnected-(IC1A-PB1-Pad47)") (class "Default")
      (node (ref "IC1") (pin "47") (pinfunction "PB1_47") (pintype "bidirectional"))
    )
    (net (code "58") (name "unconnected-(IC1A-PB3-Pad133)") (class "Default")
      (node (ref "IC1") (pin "133") (pinfunction "PB3_133") (pintype "bidirectional"))
    )
    (net (code "59") (name "unconnected-(IC1A-PB4-Pad134)") (class "Default")
      (node (ref "IC1") (pin "134") (pinfunction "PB4_134") (pintype "bidirectional"))
    )
    (net (code "60") (name "unconnected-(IC1A-PB5-Pad135)") (class "Default")
      (node (ref "IC1") (pin "135") (pinfunction "PB5_135") (pintype "bidirectional"))
    )
    (net (code "61") (name "unconnected-(IC1A-PB6-Pad136)") (class "Default")
      (node (ref "IC1") (pin "136") (pinfunction "PB6_136") (pintype "bidirectional"))
    )
    (net (code "62") (name "unconnected-(IC1A-PB7-Pad137)") (class "Default")
      (node (ref "IC1") (pin "137") (pinfunction "PB7_137") (pintype "bidirectional"))
    )
    (net (code "63") (name "unconnected-(IC1A-PB8-Pad139)") (class "Default")
      (node (ref "IC1") (pin "139") (pinfunction "PB8_139") (pintype "bidirectional"))
    )
    (net (code "64") (name "unconnected-(IC1A-PB9-Pad140)") (class "Default")
      (node (ref "IC1") (pin "140") (pinfunction "PB9_140") (pintype "bidirectional"))
    )
    (net (code "65") (name "unconnected-(IC1A-PB14-Pad75)") (class "Default")
      (node (ref "IC1") (pin "75") (pinfunction "PB14_75") (pintype "bidirectional"))
    )
    (net (code "66") (name "unconnected-(IC1A-PB15-Pad76)") (class "Default")
      (node (ref "IC1") (pin "76") (pinfunction "PB15_76") (pintype "bidirectional"))
    )
    (net (code "67") (name "unconnected-(IC1A-PC0-Pad26)") (class "Default")
      (node (ref "IC1") (pin "26") (pinfunction "PC0_26") (pintype "bidirectional"))
    )
    (net (code "68") (name "unconnected-(IC1A-PC4-Pad44)") (class "Default")
      (node (ref "IC1") (pin "44") (pinfunction "PC4_44") (pintype "bidirectional"))
    )
    (net (code "69") (name "unconnected-(IC1A-PC5-Pad45)") (class "Default")
      (node (ref "IC1") (pin "45") (pinfunction "PC5_45") (pintype "bidirectional"))
    )
    (net (code "70") (name "unconnected-(IC1A-PC6-Pad96)") (class "Default")
      (node (ref "IC1") (pin "96") (pinfunction "PC6_96") (pintype "bidirectional"))
    )
    (net (code "71") (name "unconnected-(IC1A-PC7-Pad97)") (class "Default")
      (node (ref "IC1") (pin "97") (pinfunction "PC7_97") (pintype "bidirectional"))
    )
    (net (code "72") (name "unconnected-(IC1A-PC8-Pad98)") (class "Default")
      (node (ref "IC1") (pin "98") (pinfunction "PC8_98") (pintype "bidirectional"))
    )
    (net (code "73") (name "unconnected-(IC1A-PC9-Pad99)") (class "Default")
      (node (ref "IC1") (pin "99") (pinfunction "PC9_99") (pintype "bidirectional"))
    )
    (net (code "74") (name "unconnected-(IC1A-PC10-Pad111)") (class "Default")
      (node (ref "IC1") (pin "111") (pinfunction "PC10_111") (pintype "bidirectional"))
    )
    (net (code "75") (name "unconnected-(IC1A-PC11-Pad112)") (class "Default")
      (node (ref "IC1") (pin "112") (pinfunction "PC11_112") (pintype "bidirectional"))
    )
    (net (code "76") (name "unconnected-(IC1A-PC12-Pad113)") (class "Default")
      (node (ref "IC1") (pin "113") (pinfunction "PC12_113") (pintype "bidirectional"))
    )
    (net (code "77") (name "unconnected-(IC1A-PC13-Pad7)") (class "Default")
      (node (ref "IC1") (pin "7") (pinfunction "PC13_7") (pintype "bidirectional"))
    )
    (net (code "78") (name "unconnected-(IC1A-PC14-Pad8)") (class "Default")
      (node (ref "IC1") (pin "8") (pinfunction "PC14_8") (pintype "bidirectional"))
    )
    (net (code "79") (name "unconnected-(IC1A-PC15-Pad9)") (class "Default")
      (node (ref "IC1") (pin "9") (pinfunction "PC15_9") (pintype "bidirectional"))
    )
    (net (code "80") (name "unconnected-(IC1A-PD0-Pad114)") (class "Default")
      (node (ref "IC1") (pin "114") (pinfunction "PD0_114") (pintype "bidirectional"))
    )
    (net (code "81") (name "unconnected-(IC1A-PD1-Pad115)") (class "Default")
      (node (ref "IC1") (pin "115") (pinfunction "PD1_115") (pintype "bidirectional"))
    )
    (net (code "82") (name "unconnected-(IC1A-PD2-Pad116)") (class "Default")
      (node (ref "IC1") (pin "116") (pinfunction "PD2_116") (pintype "bidirectional"))
    )
    (net (code "83") (name "unconnected-(IC1A-PD3-Pad117)") (class "Default")
      (node (ref "IC1") (pin "117") (pinfunction "PD3_117") (pintype "bidirectional"))
    )
    (net (code "84") (name "unconnected-(IC1A-PD4-Pad118)") (class "Default")
      (node (ref "IC1") (pin "118") (pinfunction "PD4_118") (pintype "bidirectional"))
    )
    (net (code "85") (name "unconnected-(IC1A-PD5-Pad119)") (class "Default")
      (node (ref "IC1") (pin "119") (pinfunction "PD5_119") (pintype "bidirectional"))
    )
    (net (code "86") (name "unconnected-(IC1A-PD6-Pad122)") (class "Default")
      (node (ref "IC1") (pin "122") (pinfunction "PD6_122") (pintype "bidirectional"))
    )
    (net (code "87") (name "unconnected-(IC1A-PD7-Pad123)") (class "Default")
      (node (ref "IC1") (pin "123") (pinfunction "PD7_123") (pintype "bidirectional"))
    )
    (net (code "88") (name "unconnected-(IC1A-PD8-Pad77)") (class "Default")
      (node (ref "IC1") (pin "77") (pinfunction "PD8_77") (pintype "bidirectional"))
    )
    (net (code "89") (name "unconnected-(IC1A-PD9-Pad78)") (class "Default")
      (node (ref "IC1") (pin "78") (pinfunction "PD9_78") (pintype "bidirectional"))
    )
    (net (code "90") (name "unconnected-(IC1A-PD10-Pad79)") (class "Default")
      (node (ref "IC1") (pin "79") (pinfunction "PD10_79") (pintype "bidirectional"))
    )
    (net (code "91") (name "unconnected-(IC1A-PD11-Pad80)") (class "Default")
      (node (ref "IC1") (pin "80") (pinfunction "PD11_80") (pintype "bidirectional"))
    )
    (net (code "92") (name "unconnected-(IC1A-PD12-Pad81)") (class "Default")
      (node (ref "IC1") (pin "81") (pinfunction "PD12_81") (pintype "bidirectional"))
    )
    (net (code "93") (name "unconnected-(IC1A-PD13-Pad82)") (class "Default")
      (node (ref "IC1") (pin "82") (pinfunction "PD13_82") (pintype "bidirectional"))
    )
    (net (code "94") (name "unconnected-(IC1A-PD14-Pad85)") (class "Default")
      (node (ref "IC1") (pin "85") (pinfunction "PD14_85") (pintype "bidirectional"))
    )
    (net (code "95") (name "unconnected-(IC1A-PD15-Pad86)") (class "Default")
      (node (ref "IC1") (pin "86") (pinfunction "PD15_86") (pintype "bidirectional"))
    )
    (net (code "96") (name "unconnected-(IC1A-PE0-Pad141)") (class "Default")
      (node (ref "IC1") (pin "141") (pinfunction "PE0_141") (pintype "bidirectional"))
    )
    (net (code "97") (name "unconnected-(IC1A-PE1-Pad142)") (class "Default")
      (node (ref "IC1") (pin "142") (pinfunction "PE1_142") (pintype "bidirectional"))
    )
    (net (code "98") (name "unconnected-(IC1A-PE2-Pad1)") (class "Default")
      (node (ref "IC1") (pin "1") (pinfunction "PE2_1") (pintype "bidirectional"))
    )
    (net (code "99") (name "unconnected-(IC1A-PE3-Pad2)") (class "Default")
      (node (ref "IC1") (pin "2") (pinfunction "PE3_2") (pintype "bidirectional"))
    )
    (net (code "100") (name "unconnected-(IC1A-PE4-Pad3)") (class "Default")
      (node (ref "IC1") (pin "3") (pinfunction "PE4_3") (pintype "bidirectional"))
    )
    (net (code "101") (name "unconnected-(IC1A-PE5-Pad4)") (class "Default")
      (node (ref "IC1") (pin "4") (pinfunction "PE5_4") (pintype "bidirectional"))
    )
    (net (code "102") (name "unconnected-(IC1A-PE6-Pad5)") (class "Default")
      (node (ref "IC1") (pin "5") (pinfunction "PE6_5") (pintype "bidirectional"))
    )
    (net (code "103") (name "unconnected-(IC1A-PE7-Pad58)") (class "Default")
      (node (ref "IC1") (pin "58") (pinfunction "PE7_58") (pintype "bidirectional"))
    )
    (net (code "104") (name "unconnected-(IC1A-PE8-Pad59)") (class "Default")
      (node (ref "IC1") (pin "59") (pinfunction "PE8_59") (pintype "bidirectional"))
    )
    (net (code "105") (name "unconnected-(IC1A-PE9-Pad60)") (class "Default")
      (node (ref "IC1") (pin "60") (pinfunction "PE9_60") (pintype "bidirectional"))
    )
    (net (code "106") (name "unconnected-(IC1A-PE10-Pad63)") (class "Default")
      (node (ref "IC1") (pin "63") (pinfunction "PE10_63") (pintype "bidirectional"))
    )
    (net (code "107") (name "unconnected-(IC1A-PE11-Pad64)") (class "Default")
      (node (ref "IC1") (pin "64") (pinfunction "PE11_64") (pintype "bidirectional"))
    )
    (net (code "108") (name "unconnected-(IC1A-PE13-Pad66)") (class "Default")
      (node (ref "IC1") (pin "66") (pinfunction "PE13_66") (pintype "bidirectional"))
    )
    (net (code "109") (name "unconnected-(IC1A-PE14-Pad67)") (class "Default")
      (node (ref "IC1") (pin "67") (pinfunction "PE14_67") (pintype "bidirectional"))
    )
    (net (code "110") (name "unconnected-(IC1A-PE15-Pad68)") (class "Default")
      (node (ref "IC1") (pin "68") (pinfunction "PE15_68") (pintype "bidirectional"))
    )
    (net (code "111") (name "unconnected-(IC1A-PF0-Pad10)") (class "Default")
      (node (ref "IC1") (pin "10") (pinfunction "PF0_10") (pintype "bidirectional"))
    )
    (net (code "112") (name "unconnected-(IC1A-PF1-Pad11)") (class "Default")
      (node (ref "IC1") (pin "11") (pinfunction "PF1_11") (pintype "bidirectional"))
    )
    (net (code "113") (name "unconnected-(IC1A-PF2-Pad12)") (class "Default")
      (node (ref "IC1") (pin "12") (pinfunction "PF2_12") (pintype "bidirectional"))
    )
    (net (code "114") (name "unconnected-(IC1A-PF3-Pad13)") (class "Default")
      (node (ref "IC1") (pin "13") (pinfunction "PF3_13") (pintype "bidirectional"))
    )
    (net (code "115") (name "unconnected-(IC1A-PF4-Pad14)") (class "Default")
      (node (ref "IC1") (pin "14") (pinfunction "PF4_14") (pintype "bidirectional"))
    )
    (net (code "116") (name "unconnected-(IC1A-PF5-Pad15)") (class "Default")
      (node (ref "IC1") (pin "15") (pinfunction "PF5_15") (pintype "bidirectional"))
    )
    (net (code "117") (name "unconnected-(IC1A-PF6-Pad18)") (class "Default")
      (node (ref "IC1") (pin "18") (pinfunction "PF6_18") (pintype "bidirectional"))
    )
    (net (code "118") (name "unconnected-(IC1A-PF7-Pad19)") (class "Default")
      (node (ref "IC1") (pin "19") (pinfunction "PF7_19") (pintype "bidirectional"))
    )
    (net (code "119") (name "unconnected-(IC1A-PF8-Pad20)") (class "Default")
      (node (ref "IC1") (pin "20") (pinfunction "PF8_20") (pintype "bidirectional"))
    )
    (net (code "120") (name "unconnected-(IC1A-PF11-Pad49)") (class "Default")
      (node (ref "IC1") (pin "49") (pinfunction "PF11_49") (pintype "bidirectional"))
    )
    (net (code "121") (name "unconnected-(IC1A-PF12-Pad50)") (class "Default")
      (node (ref "IC1") (pin "50") (pinfunction "PF12_50") (pintype "bidirectional"))
    )
    (net (code "122") (name "unconnected-(IC1A-PF13-Pad53)") (class "Default")
      (node (ref "IC1") (pin "53") (pinfunction "PF13_53") (pintype "bidirectional"))
    )
    (net (code "123") (name "unconnected-(IC1A-PF14-Pad54)") (class "Default")
      (node (ref "IC1") (pin "54") (pinfunction "PF14_54") (pintype "bidirectional"))
    )
    (net (code "124") (name "unconnected-(IC1A-PF15-Pad55)") (class "Default")
      (node (ref "IC1") (pin "55") (pinfunction "PF15_55") (pintype "bidirectional"))
    )
    (net (code "125") (name "unconnected-(IC1A-PG0-Pad56)") (class "Default")
      (node (ref "IC1") (pin "56") (pinfunction "PG0_56") (pintype "bidirectional"))
    )
    (net (code "126") (name "unconnected-(IC1A-PG1-Pad57)") (class "Default")
      (node (ref "IC1") (pin "57") (pinfunction "PG1_57") (pintype "bidirectional"))
    )
    (net (code "127") (name "unconnected-(IC1A-PG2-Pad87)") (class "Default")
      (node (ref "IC1") (pin "87") (pinfunction "PG2_87") (pintype "bidirectional"))
    )
    (net (code "128") (name "unconnected-(IC1A-PG3-Pad88)") (class "Default")
      (node (ref "IC1") (pin "88") (pinfunction "PG3_88") (pintype "bidirectional"))
    )
    (net (code "129") (name "unconnected-(IC1A-PG4-Pad89)") (class "Default")
      (node (ref "IC1") (pin "89") (pinfunction "PG4_89") (pintype "bidirectional"))
    )
    (net (code "130") (name "unconnected-(IC1A-PG5-Pad90)") (class "Default")
      (node (ref "IC1") (pin "90") (pinfunction "PG5_90") (pintype "bidirectional"))
    )
    (net (code "131") (name "unconnected-(IC1A-PG6-Pad91)") (class "Default")
      (node (ref "IC1") (pin "91") (pinfunction "PG6_91") (pintype "bidirectional"))
    )
    (net (code "132") (name "unconnected-(IC1A-PG7-Pad92)") (class "Default")
      (node (ref "IC1") (pin "92") (pinfunction "PG7_92") (pintype "bidirectional"))
    )
    (net (code "133") (name "unconnected-(IC1A-PG8-Pad93)") (class "Default")
      (node (ref "IC1") (pin "93") (pinfunction "PG8_93") (pintype "bidirectional"))
    )
    (net (code "134") (name "unconnected-(IC1A-PG9-Pad124)") (class "Default")
      (node (ref "IC1") (pin "124") (pinfunction "PG9_124") (pintype "bidirectional"))
    )
    (net (code "135") (name "unconnected-(IC1A-PG10-Pad125)") (class "Default")
      (node (ref "IC1") (pin "125") (pinfunction "PG10_125") (pintype "bidirectional"))
    )
    (net (code "136") (name "unconnected-(IC1A-PG11-Pad126)") (class "Default")
      (node (ref "IC1") (pin "126") (pinfunction "PG11_126") (pintype "bidirectional"))
    )
    (net (code "137") (name "unconnected-(IC1A-PG12-Pad127)") (class "Default")
      (node (ref "IC1") (pin "127") (pinfunction "PG12_127") (pintype "bidirectional"))
    )
    (net (code "138") (name "unconnected-(IC1A-PG13-Pad128)") (class "Default")
      (node (ref "IC1") (pin "128") (pinfunction "PG13_128") (pintype "bidirectional"))
    )
    (net (code "139") (name "unconnected-(IC1A-PG14-Pad129)") (class "Default")
      (node (ref "IC1") (pin "129") (pinfunction "PG14_129") (pintype "bidirectional"))
    )
    (net (code "140") (name "unconnected-(IC1A-PG15-Pad132)") (class "Default")
      (node (ref "IC1") (pin "132") (pinfunction "PG15_132") (pintype "bidirectional"))
    )
    (net (code "141") (name "unconnected-(RT9013-1-NC-Pad4)") (class "Default")
      (node (ref "RT9013-1") (pin "4") (pinfunction "NC_4") (pintype "bidirectional"))
    )
    (net (code "142") (name "unconnected-(SW-1-B-PadP$1)") (class "Default")
      (node (ref "SW-1") (pin "P$1") (pinfunction "B_P$1") (pintype "bidirectional"))
    )
    (net (code "143") (name "unconnected-(SW3P-2-COM-Pad3)") (class "Default")
      (node (ref "SW3P-2") (pin "3") (pinfunction "COM_3") (pintype "bidirectional"))
    )
    (net (code "144") (name "unconnected-(USB2-ID-Pad4)") (class "Default")
      (node (ref "USB2") (pin "4") (pinfunction "ID_4") (pintype "bidirectional"))
    )
    (net (code "145") (name "unconnected-(Y1-1-Pad4)") (class "Default")
      (node (ref "Y1") (pin "4") (pinfunction "1_4") (pintype "bidirectional"))
    )
    (net (code "146") (name "unconnected-(Y1-3-Pad2)") (class "Default")
      (node (ref "Y1") (pin "2") (pinfunction "3_2") (pintype "bidirectional"))
    )
  )
)
